# BOT-TOP.net
KiCad netlist of a schematic drawn in Altium Designer
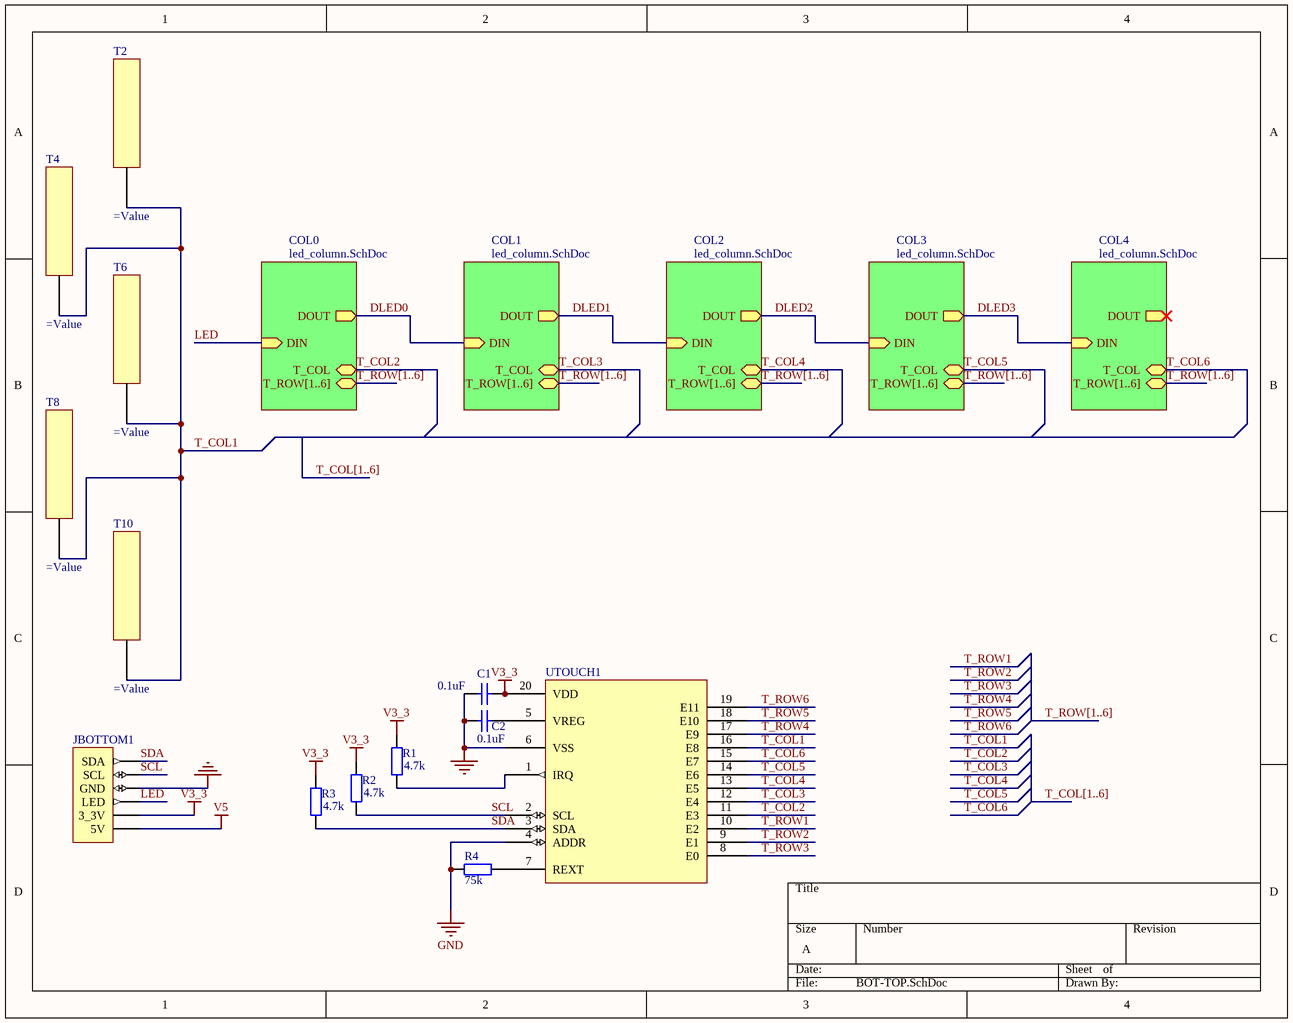
[diagram p0: BOT-TOP.SchDoc]

(export (version "E")
  (design (tool "Eeschema 10.0.6"))
  (components
    (comp (ref "C1")
      (value "0.1uF")
      (footprint "CAPC2012L")
      (description "Capacitor")
      (fields (field (name "PUBLISHER") "Altium Limited"))
      (libsource (lib "*") (part "Cap"))
    )
    (comp (ref "C2")
      (value "0.1uF")
      (footprint "CAPC2012L")
      (description "Capacitor")
      (fields (field (name "PUBLISHER") "Altium Limited"))
      (libsource (lib "*") (part "Cap"))
    )
    (comp (ref "JBOTTOM1")
      (value "~")
      (footprint "HDR1X6")
      (description "Header, 6-Pin")
      (fields (field (name "PUBLISHER") "Altium Limited"))
      (libsource (lib "*") (part "Header 6"))
    )
    (comp (ref "R1")
      (value "4.7k")
      (footprint "RESC2012L")
      (description "Resistor")
      (fields (field (name "PUBLISHER") "Altium Limited"))
      (libsource (lib "") (part "Res2_1"))
    )
    (comp (ref "R2")
      (value "4.7k")
      (footprint "RESC2012L")
      (description "Resistor")
      (fields (field (name "PUBLISHER") "Altium Limited"))
      (libsource (lib "") (part "Res2_1"))
    )
    (comp (ref "R3")
      (value "4.7k")
      (footprint "RESC2012L")
      (description "Resistor")
      (fields (field (name "PUBLISHER") "Altium Limited"))
      (libsource (lib "") (part "Res2_1"))
    )
    (comp (ref "R4")
      (value "75k")
      (footprint "RESC2012L")
      (description "Resistor")
      (fields (field (name "PUBLISHER") "Altium Limited"))
      (libsource (lib "*") (part "Res2"))
    )
    (comp (ref "T2")
      (value "~")
      (footprint "TouchStrip_Vert")
      (libsource (lib "components_top") (part "TouchStrip"))
    )
    (comp (ref "T4")
      (value "~")
      (footprint "TouchStrip_Vert")
      (libsource (lib "components_top") (part "TouchStrip"))
    )
    (comp (ref "T6")
      (value "~")
      (footprint "TouchStrip_Vert")
      (libsource (lib "components_top") (part "TouchStrip"))
    )
    (comp (ref "T8")
      (value "~")
      (footprint "TouchStrip_Vert")
      (libsource (lib "components_top") (part "TouchStrip"))
    )
    (comp (ref "T10")
      (value "~")
      (footprint "TouchStrip_Vert")
      (libsource (lib "components_top") (part "TouchStrip"))
    )
    (comp (ref "UTOUCH1") (value "~") (footprint "MPR121") (libsource (lib "components_top") (part "MPR121")))
  )
  (nets
    (net (code "6") (name "/LED") (class "Default")
      (node (ref "JBOTTOM1") (pin "3") (pinfunction "LED_3") (pintype "output"))
    )
    (net (code "7") (name "/SCL") (class "Default")
      (node (ref "JBOTTOM1") (pin "5") (pinfunction "SCL_5") (pintype "bidirectional"))
      (node (ref "R2") (pin "2") (pinfunction "2_2") (pintype "passive"))
      (node (ref "UTOUCH1") (pin "2") (pinfunction "SCL_2") (pintype "bidirectional"))
    )
    (net (code "8") (name "/SDA") (class "Default")
      (node (ref "JBOTTOM1") (pin "6") (pinfunction "SDA_6") (pintype "output"))
      (node (ref "R3") (pin "2") (pinfunction "2_2") (pintype "passive"))
      (node (ref "UTOUCH1") (pin "3") (pinfunction "SDA_3") (pintype "bidirectional"))
    )
    (net (code "9") (name "/T_COL1") (class "Default")
      (node (ref "T10") (pin "0") (pinfunction "0_0") (pintype "passive"))
      (node (ref "T2") (pin "0") (pinfunction "0_0") (pintype "passive"))
      (node (ref "T4") (pin "0") (pinfunction "0_0") (pintype "passive"))
      (node (ref "T6") (pin "0") (pinfunction "0_0") (pintype "passive"))
      (node (ref "T8") (pin "0") (pinfunction "0_0") (pintype "passive"))
      (node (ref "UTOUCH1") (pin "16") (pinfunction "E8_16") (pintype "passive"))
    )
    (net (code "10") (name "/T_COL2") (class "Default")
      (node (ref "UTOUCH1") (pin "11") (pinfunction "E3_11") (pintype "passive"))
    )
    (net (code "11") (name "/T_COL3") (class "Default")
      (node (ref "UTOUCH1") (pin "12") (pinfunction "E4_12") (pintype "passive"))
    )
    (net (code "12") (name "/T_COL4") (class "Default")
      (node (ref "UTOUCH1") (pin "13") (pinfunction "E5_13") (pintype "passive"))
    )
    (net (code "13") (name "/T_COL5") (class "Default")
      (node (ref "UTOUCH1") (pin "14") (pinfunction "E6_14") (pintype "passive"))
    )
    (net (code "14") (name "/T_COL6") (class "Default")
      (node (ref "UTOUCH1") (pin "15") (pinfunction "E7_15") (pintype "passive"))
    )
    (net (code "16") (name "/T_ROW1") (class "Default")
      (node (ref "UTOUCH1") (pin "10") (pinfunction "E2_10") (pintype "passive"))
    )
    (net (code "17") (name "/T_ROW2") (class "Default")
      (node (ref "UTOUCH1") (pin "9") (pinfunction "E1_9") (pintype "passive"))
    )
    (net (code "18") (name "/T_ROW3") (class "Default")
      (node (ref "UTOUCH1") (pin "8") (pinfunction "E0_8") (pintype "passive"))
    )
    (net (code "19") (name "/T_ROW4") (class "Default")
      (node (ref "UTOUCH1") (pin "17") (pinfunction "E9_17") (pintype "passive"))
    )
    (net (code "20") (name "/T_ROW5") (class "Default")
      (node (ref "UTOUCH1") (pin "18") (pinfunction "E10_18") (pintype "passive"))
    )
    (net (code "21") (name "/T_ROW6") (class "Default")
      (node (ref "UTOUCH1") (pin "19") (pinfunction "E11_19") (pintype "passive"))
    )
    (net (code "23") (name "GND") (class "Default")
      (node (ref "C1") (pin "1") (pinfunction "1_1") (pintype "passive"))
      (node (ref "C2") (pin "1") (pinfunction "1_1") (pintype "passive"))
      (node (ref "JBOTTOM1") (pin "4") (pinfunction "GND_4") (pintype "bidirectional"))
      (node (ref "R4") (pin "1") (pinfunction "1_1") (pintype "passive"))
      (node (ref "UTOUCH1") (pin "4") (pinfunction "ADDR_4") (pintype "bidirectional"))
      (node (ref "UTOUCH1") (pin "6") (pinfunction "VSS_6") (pintype "power_in"))
    )
    (net (code "24") (name "Net-(UTOUCH1-IRQ)") (class "Default")
      (node (ref "R1") (pin "2") (pinfunction "2_2") (pintype "passive"))
      (node (ref "UTOUCH1") (pin "1") (pinfunction "IRQ_1") (pintype "output"))
    )
    (net (code "25") (name "Net-(UTOUCH1-REXT)") (class "Default")
      (node (ref "R4") (pin "2") (pinfunction "2_2") (pintype "passive"))
      (node (ref "UTOUCH1") (pin "7") (pinfunction "REXT_7") (pintype "passive"))
    )
    (net (code "26") (name "Net-(UTOUCH1-VREG)") (class "Default")
      (node (ref "C2") (pin "2") (pinfunction "2_2") (pintype "passive"))
      (node (ref "UTOUCH1") (pin "5") (pinfunction "VREG_5") (pintype "power_in"))
    )
    (net (code "27") (name "V3_3") (class "Default")
      (node (ref "C1") (pin "2") (pinfunction "2_2") (pintype "passive"))
      (node (ref "JBOTTOM1") (pin "2") (pinfunction "3_3V_2") (pintype "power_in"))
      (node (ref "R1") (pin "1") (pinfunction "1_1") (pintype "passive"))
      (node (ref "R2") (pin "1") (pinfunction "1_1") (pintype "passive"))
      (node (ref "R3") (pin "1") (pinfunction "1_1") (pintype "passive"))
      (node (ref "UTOUCH1") (pin "20") (pinfunction "VDD_20") (pintype "power_in"))
    )
    (net (code "28") (name "V5") (class "Default")
      (node (ref "JBOTTOM1") (pin "1") (pinfunction "5V_1") (pintype "power_in"))
    )
  )
)
